# Studio_Lighting_Driver.net
KiCad netlist of a schematic drawn in Altium Designer
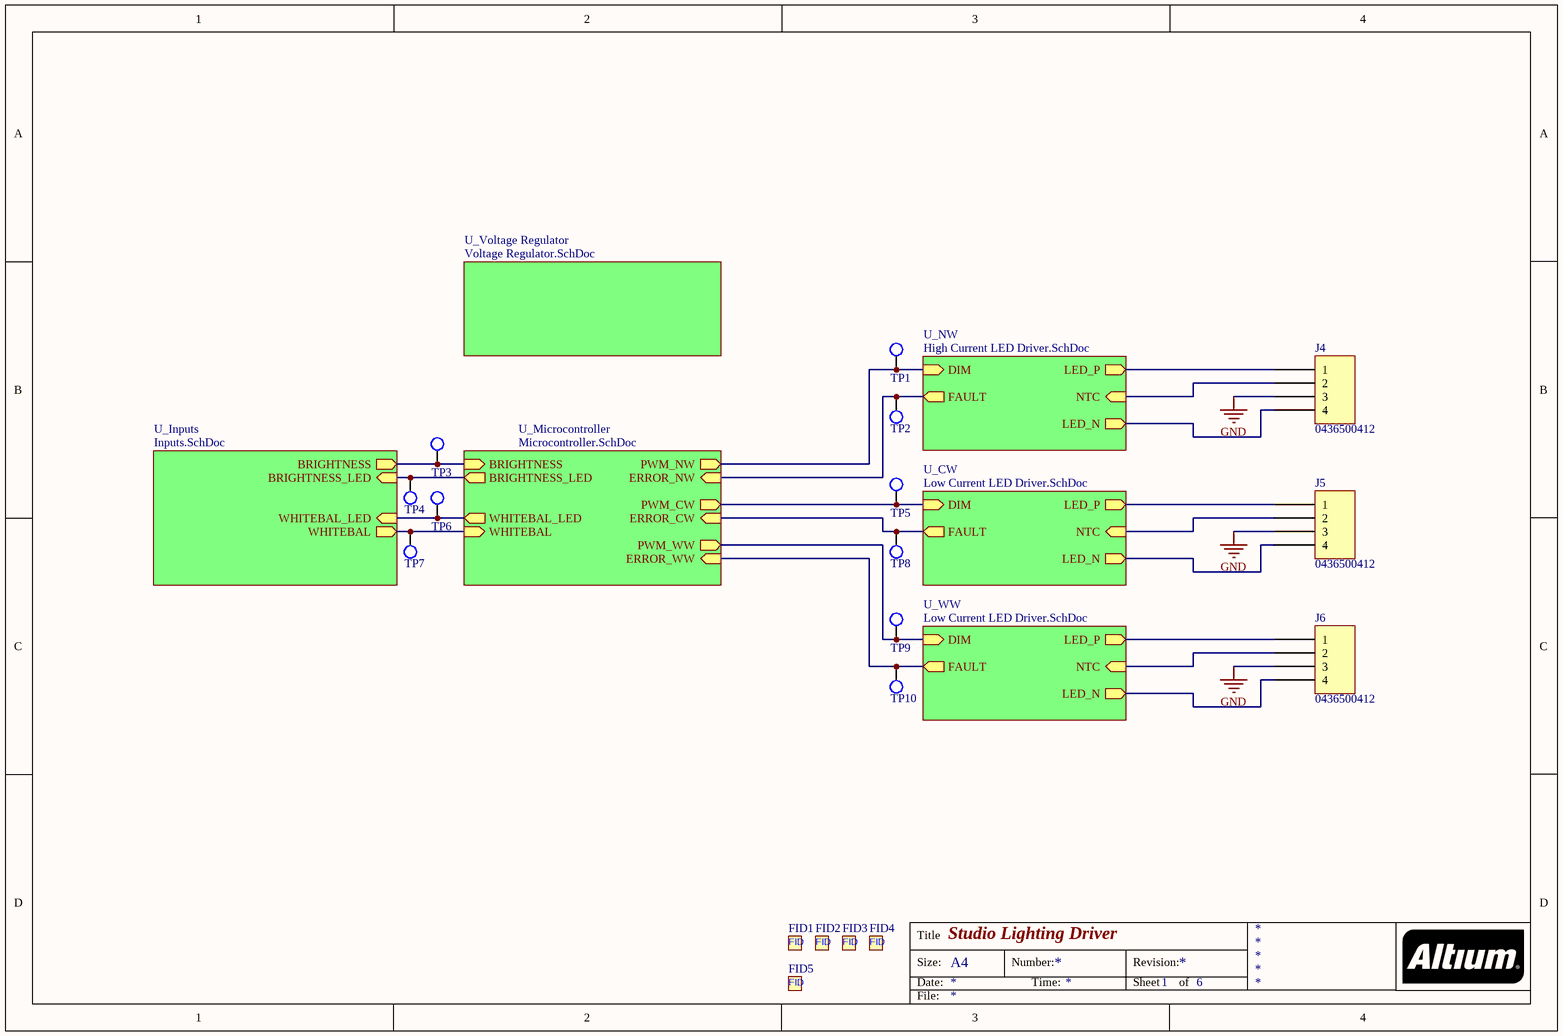
[diagram p0: Studio Lighting Driver.SchDoc]

(export (version "E")
  (design (tool "Eeschema 10.0.6"))
  (components
    (comp (ref "FID1")
      (value "Fiducial")
      (footprint "Fiducial-1mm")
      (libsource (lib "CelestialUseful") (part "Fiducial"))
    )
    (comp (ref "FID2")
      (value "Fiducial")
      (footprint "Fiducial-1mm")
      (libsource (lib "CelestialUseful") (part "Fiducial"))
    )
    (comp (ref "FID3")
      (value "Fiducial")
      (footprint "Fiducial-1mm")
      (libsource (lib "CelestialUseful") (part "Fiducial"))
    )
    (comp (ref "FID4")
      (value "Fiducial")
      (footprint "Fiducial-1mm")
      (libsource (lib "CelestialUseful") (part "Fiducial"))
    )
    (comp (ref "FID5")
      (value "Fiducial")
      (footprint "Fiducial-1mm")
      (libsource (lib "CelestialUseful") (part "Fiducial"))
    )
    (comp (ref "J4")
      (value "0436500412")
      (footprint "MOLEX 436500412")
      (description "CONN HEADER SMD R/A 4POS 3MM")
      (fields (field (name "MANUFACTURER") "Molex"))
      (libsource (lib "altiumlibrary.com") (part "4 Pin"))
    )
    (comp (ref "J5")
      (value "0436500412")
      (footprint "MOLEX 436500412")
      (description "CONN HEADER SMD R/A 4POS 3MM")
      (fields (field (name "MANUFACTURER") "Molex"))
      (libsource (lib "altiumlibrary.com") (part "4 Pin"))
    )
    (comp (ref "J6")
      (value "0436500412")
      (footprint "MOLEX 436500412")
      (description "CONN HEADER SMD R/A 4POS 3MM")
      (fields (field (name "MANUFACTURER") "Molex"))
      (libsource (lib "altiumlibrary.com") (part "4 Pin"))
    )
    (comp (ref "TP1")
      (value "Test Point")
      (footprint "TestPoint-1.5mm")
      (libsource (lib "CelestialUseful") (part "Test Point"))
    )
    (comp (ref "TP2")
      (value "Test Point")
      (footprint "TestPoint-1.5mm")
      (libsource (lib "CelestialUseful") (part "Test Point"))
    )
    (comp (ref "TP3")
      (value "Test Point")
      (footprint "TestPoint-1.5mm")
      (libsource (lib "CelestialUseful") (part "Test Point"))
    )
    (comp (ref "TP4")
      (value "Test Point")
      (footprint "TestPoint-1.5mm")
      (libsource (lib "CelestialUseful") (part "Test Point"))
    )
    (comp (ref "TP5")
      (value "Test Point")
      (footprint "TestPoint-1.5mm")
      (libsource (lib "CelestialUseful") (part "Test Point"))
    )
    (comp (ref "TP6")
      (value "Test Point")
      (footprint "TestPoint-1.5mm")
      (libsource (lib "CelestialUseful") (part "Test Point"))
    )
    (comp (ref "TP7")
      (value "Test Point")
      (footprint "TestPoint-1.5mm")
      (libsource (lib "CelestialUseful") (part "Test Point"))
    )
    (comp (ref "TP8")
      (value "Test Point")
      (footprint "TestPoint-1.5mm")
      (libsource (lib "CelestialUseful") (part "Test Point"))
    )
    (comp (ref "TP9")
      (value "Test Point")
      (footprint "TestPoint-1.5mm")
      (libsource (lib "CelestialUseful") (part "Test Point"))
    )
    (comp (ref "TP10")
      (value "Test Point")
      (footprint "TestPoint-1.5mm")
      (libsource (lib "CelestialUseful") (part "Test Point"))
    )
  )
  (nets
    (net (code "1") (name "/BRIGHTNESS") (class "Default")
      (node (ref "TP3") (pin "1") (pinfunction "TP_1") (pintype "passive"))
    )
    (net (code "2") (name "/BRIGHTNESS_LED") (class "Default")
      (node (ref "TP4") (pin "1") (pinfunction "TP_1") (pintype "passive"))
    )
    (net (code "3") (name "/FAULT") (class "Default")
      (node (ref "TP8") (pin "1") (pinfunction "TP_1") (pintype "passive"))
    )
    (net (code "4") (name "/FAULT_1") (class "Default")
      (node (ref "TP2") (pin "1") (pinfunction "TP_1") (pintype "passive"))
    )
    (net (code "5") (name "/FAULT_2") (class "Default")
      (node (ref "TP10") (pin "1") (pinfunction "TP_1") (pintype "passive"))
    )
    (net (code "6") (name "/LED_N") (class "Default")
      (node (ref "J5") (pin "4") (pinfunction "4_4") (pintype "passive"))
    )
    (net (code "7") (name "/LED_N_1") (class "Default")
      (node (ref "J6") (pin "4") (pinfunction "4_4") (pintype "passive"))
    )
    (net (code "8") (name "/LED_N_2") (class "Default")
      (node (ref "J4") (pin "4") (pinfunction "4_4") (pintype "passive"))
    )
    (net (code "9") (name "/LED_P") (class "Default")
      (node (ref "J6") (pin "1") (pinfunction "1_1") (pintype "passive"))
    )
    (net (code "10") (name "/LED_P_1") (class "Default")
      (node (ref "J5") (pin "1") (pinfunction "1_1") (pintype "passive"))
    )
    (net (code "11") (name "/LED_P_2") (class "Default")
      (node (ref "J4") (pin "1") (pinfunction "1_1") (pintype "passive"))
    )
    (net (code "12") (name "/NTC") (class "Default")
      (node (ref "J4") (pin "2") (pinfunction "2_2") (pintype "passive"))
    )
    (net (code "13") (name "/NTC_1") (class "Default")
      (node (ref "J6") (pin "2") (pinfunction "2_2") (pintype "passive"))
    )
    (net (code "14") (name "/NTC_2") (class "Default")
      (node (ref "J5") (pin "2") (pinfunction "2_2") (pintype "passive"))
    )
    (net (code "15") (name "/PWM_CW") (class "Default")
      (node (ref "TP5") (pin "1") (pinfunction "TP_1") (pintype "passive"))
    )
    (net (code "16") (name "/PWM_NW") (class "Default")
      (node (ref "TP1") (pin "1") (pinfunction "TP_1") (pintype "passive"))
    )
    (net (code "17") (name "/PWM_WW") (class "Default")
      (node (ref "TP9") (pin "1") (pinfunction "TP_1") (pintype "passive"))
    )
    (net (code "18") (name "/WHITEBAL") (class "Default")
      (node (ref "TP7") (pin "1") (pinfunction "TP_1") (pintype "passive"))
    )
    (net (code "19") (name "/WHITEBAL_LED") (class "Default")
      (node (ref "TP6") (pin "1") (pinfunction "TP_1") (pintype "passive"))
    )
    (net (code "20") (name "GND") (class "Default")
      (node (ref "J4") (pin "3") (pinfunction "3_3") (pintype "passive"))
      (node (ref "J5") (pin "3") (pinfunction "3_3") (pintype "passive"))
      (node (ref "J6") (pin "3") (pinfunction "3_3") (pintype "passive"))
    )
  )
)
